# comparator.net
KiCad netlist of a schematic drawn in EAGLE
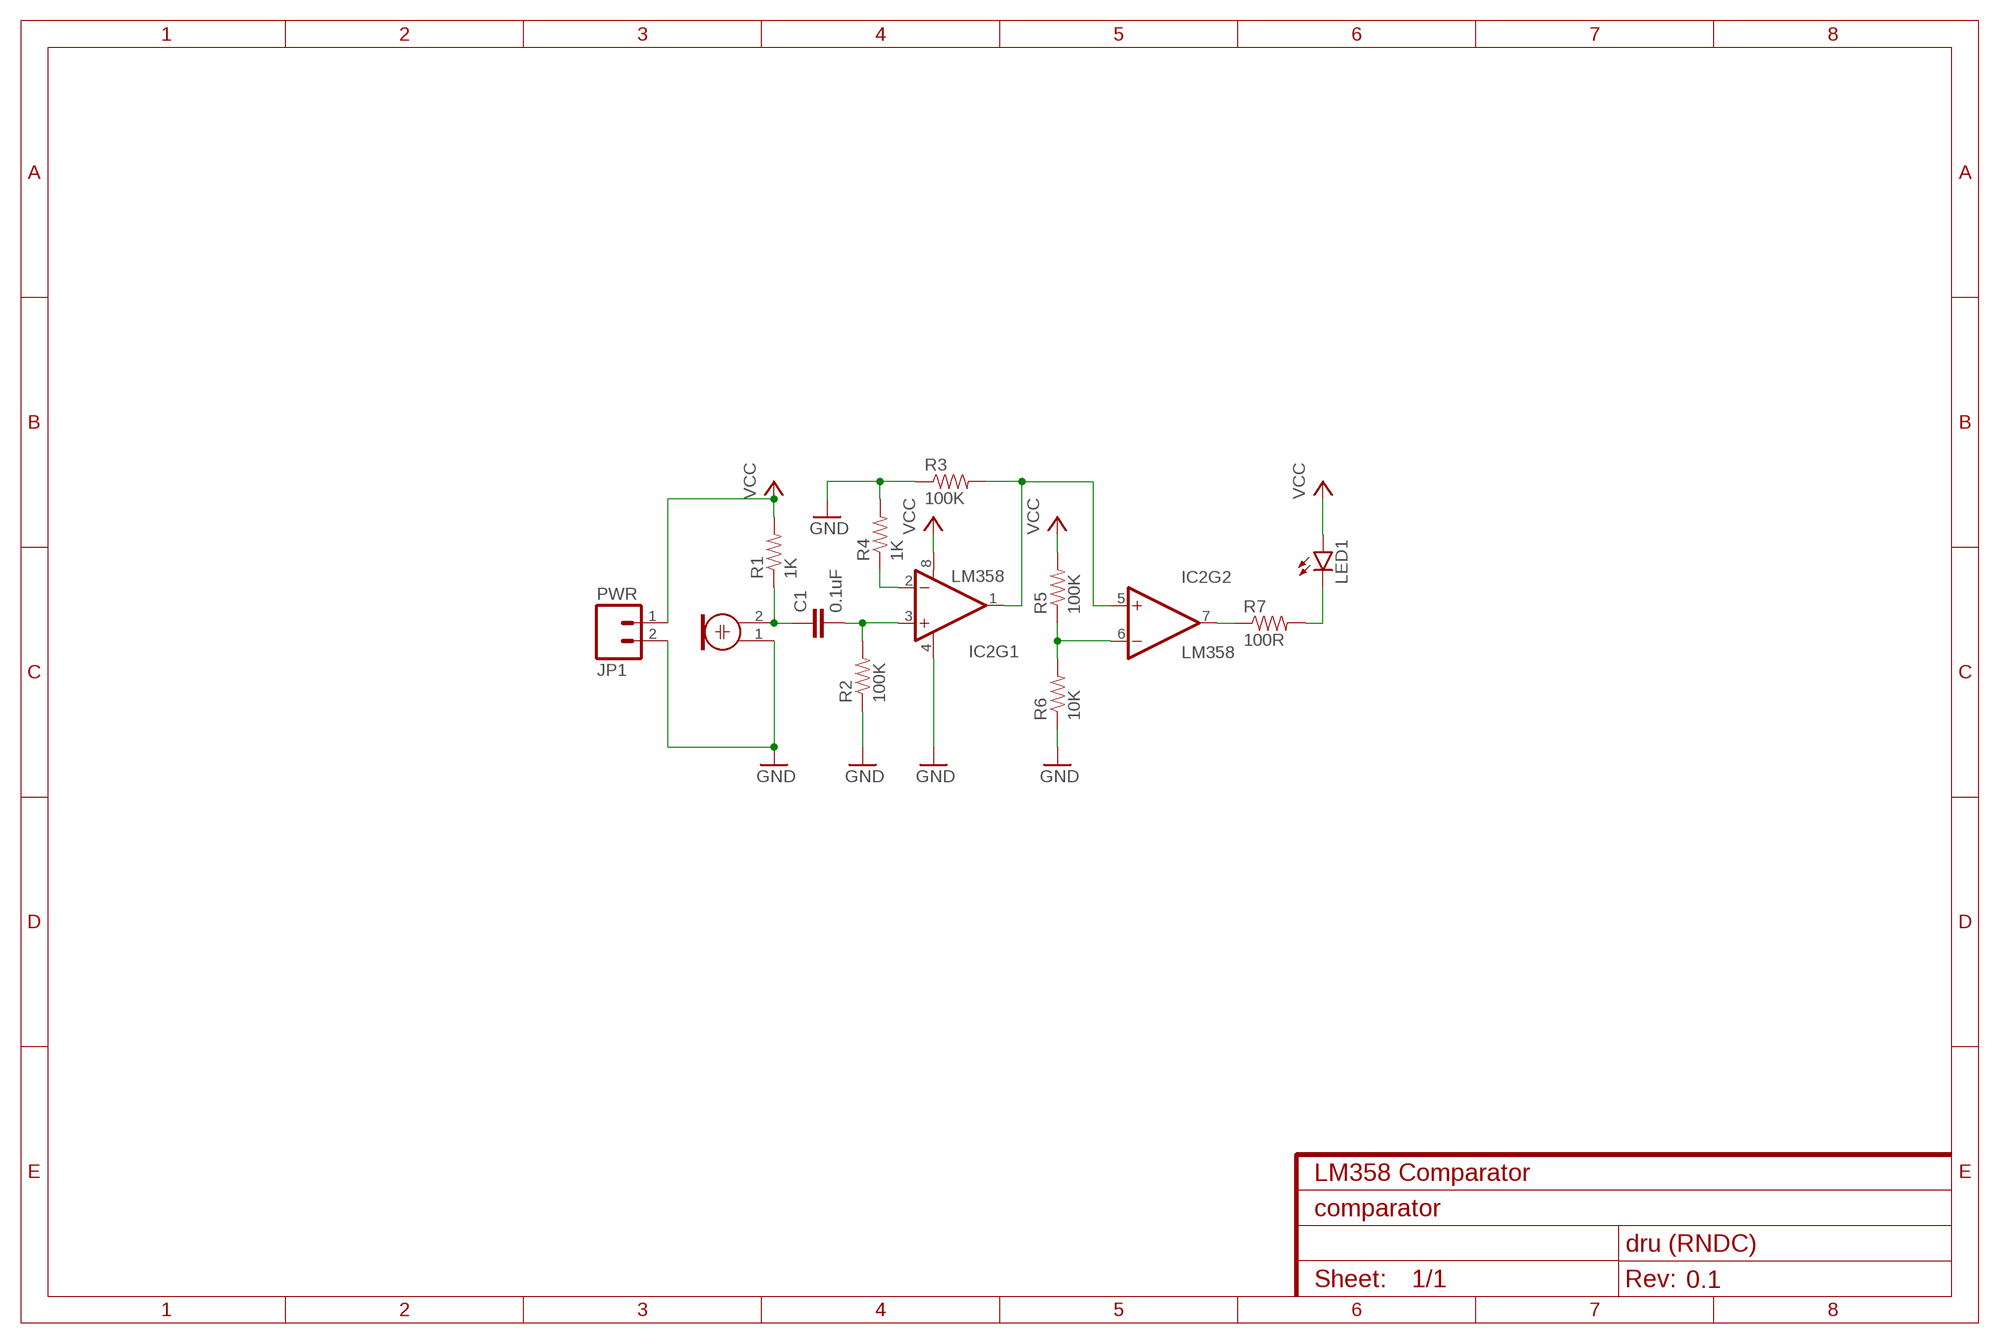
[diagram p0: schematic, sheet 1]

(export (version "E")
  (design (tool "Eeschema 10.0.6"))
  (components
    (comp (ref "C1")
      (value "0.1uF")
      (footprint "eagle-import:CAP-PTH-5MM")
      (libsource (lib "eagle-import") (part "CAPPTH1"))
    )
    (comp (ref "IC2")
      (value "LM358")
      (footprint "eagle-import:DIP08")
      (libsource (lib "eagle-import") (part "LM358"))
    )
    (comp (ref "JP1")
      (value "PWR")
      (footprint "eagle-import:1X02_LONGPADS")
      (libsource (lib "eagle-import") (part "M02PTH3"))
    )
    (comp (ref "LED1")
      (value "LED5MM")
      (footprint "eagle-import:LED5MM")
      (libsource (lib "eagle-import") (part "LED5MM"))
    )
    (comp (ref "MIC")
      (value "ELECTRET_MICROPHON-WM-61B")
      (footprint "eagle-import:WM-61B")
      (libsource (lib "eagle-import") (part "ELECTRET_MICROPHON-WM-61B"))
    )
    (comp (ref "R1")
      (value "1K")
      (footprint "eagle-import:AXIAL-0.3EZ")
      (libsource (lib "eagle-import") (part "RESISTOREZ"))
    )
    (comp (ref "R2")
      (value "100K")
      (footprint "eagle-import:AXIAL-0.3EZ")
      (libsource (lib "eagle-import") (part "RESISTOREZ"))
    )
    (comp (ref "R3")
      (value "100K")
      (footprint "eagle-import:AXIAL-0.3EZ")
      (libsource (lib "eagle-import") (part "RESISTOREZ"))
    )
    (comp (ref "R4")
      (value "1K")
      (footprint "eagle-import:AXIAL-0.3EZ")
      (libsource (lib "eagle-import") (part "RESISTOREZ"))
    )
    (comp (ref "R5")
      (value "100K")
      (footprint "eagle-import:AXIAL-0.3EZ")
      (libsource (lib "eagle-import") (part "RESISTOREZ"))
    )
    (comp (ref "R6")
      (value "10K")
      (footprint "eagle-import:AXIAL-0.3EZ")
      (libsource (lib "eagle-import") (part "RESISTOREZ"))
    )
    (comp (ref "R7")
      (value "100R")
      (footprint "eagle-import:AXIAL-0.3EZ")
      (libsource (lib "eagle-import") (part "RESISTOREZ"))
    )
  )
  (nets
    (net (code "1") (name "GND") (class "Default")
      (node (ref "IC2") (pin "4") (pinfunction "V-_4") (pintype "power_in"))
      (node (ref "JP1") (pin "2") (pinfunction "2_2") (pintype "passive"))
      (node (ref "MIC") (pin "1") (pinfunction "1_1") (pintype "passive"))
      (node (ref "R2") (pin "P$1") (pinfunction "1_P$1") (pintype "passive"))
      (node (ref "R3") (pin "P$1") (pinfunction "1_P$1") (pintype "passive"))
      (node (ref "R4") (pin "P$2") (pinfunction "2_P$2") (pintype "passive"))
      (node (ref "R6") (pin "P$1") (pinfunction "1_P$1") (pintype "passive"))
    )
    (net (code "2") (name "Net-(IC2A-+IN)") (class "Default")
      (node (ref "C1") (pin "2") (pinfunction "2_2") (pintype "passive"))
      (node (ref "IC2") (pin "3") (pinfunction "+IN_3") (pintype "input"))
      (node (ref "R2") (pin "P$2") (pinfunction "2_P$2") (pintype "passive"))
    )
    (net (code "3") (name "Net-(IC2A--IN)") (class "Default")
      (node (ref "IC2") (pin "2") (pinfunction "-IN_2") (pintype "input"))
      (node (ref "R4") (pin "P$1") (pinfunction "1_P$1") (pintype "passive"))
    )
    (net (code "4") (name "Net-(IC2A-OUT)") (class "Default")
      (node (ref "IC2") (pin "1") (pinfunction "OUT_1") (pintype "output"))
      (node (ref "IC2") (pin "5") (pinfunction "+IN_5") (pintype "input"))
      (node (ref "R3") (pin "P$2") (pinfunction "2_P$2") (pintype "passive"))
    )
    (net (code "5") (name "Net-(IC2B--IN)") (class "Default")
      (node (ref "IC2") (pin "6") (pinfunction "-IN_6") (pintype "input"))
      (node (ref "R5") (pin "P$1") (pinfunction "1_P$1") (pintype "passive"))
      (node (ref "R6") (pin "P$2") (pinfunction "2_P$2") (pintype "passive"))
    )
    (net (code "6") (name "Net-(IC2B-OUT)") (class "Default")
      (node (ref "IC2") (pin "7") (pinfunction "OUT_7") (pintype "output"))
      (node (ref "R7") (pin "P$1") (pinfunction "1_P$1") (pintype "passive"))
    )
    (net (code "7") (name "Net-(LED1-C)") (class "Default")
      (node (ref "LED1") (pin "K") (pinfunction "C_K") (pintype "passive"))
      (node (ref "R7") (pin "P$2") (pinfunction "2_P$2") (pintype "passive"))
    )
    (net (code "8") (name "Net-(R1-1)") (class "Default")
      (node (ref "C1") (pin "1") (pinfunction "1_1") (pintype "passive"))
      (node (ref "MIC") (pin "2") (pinfunction "2_2") (pintype "passive"))
      (node (ref "R1") (pin "P$1") (pinfunction "1_P$1") (pintype "passive"))
    )
    (net (code "9") (name "VCC") (class "Default")
      (node (ref "IC2") (pin "8") (pinfunction "V+_8") (pintype "power_in"))
      (node (ref "JP1") (pin "1") (pinfunction "1_1") (pintype "passive"))
      (node (ref "LED1") (pin "A") (pinfunction "A_A") (pintype "passive"))
      (node (ref "R1") (pin "P$2") (pinfunction "2_P$2") (pintype "passive"))
      (node (ref "R5") (pin "P$2") (pinfunction "2_P$2") (pintype "passive"))
    )
  )
)
